# FIT_TCM_SI53301.net
KiCad netlist of a schematic drawn in Altium Designer
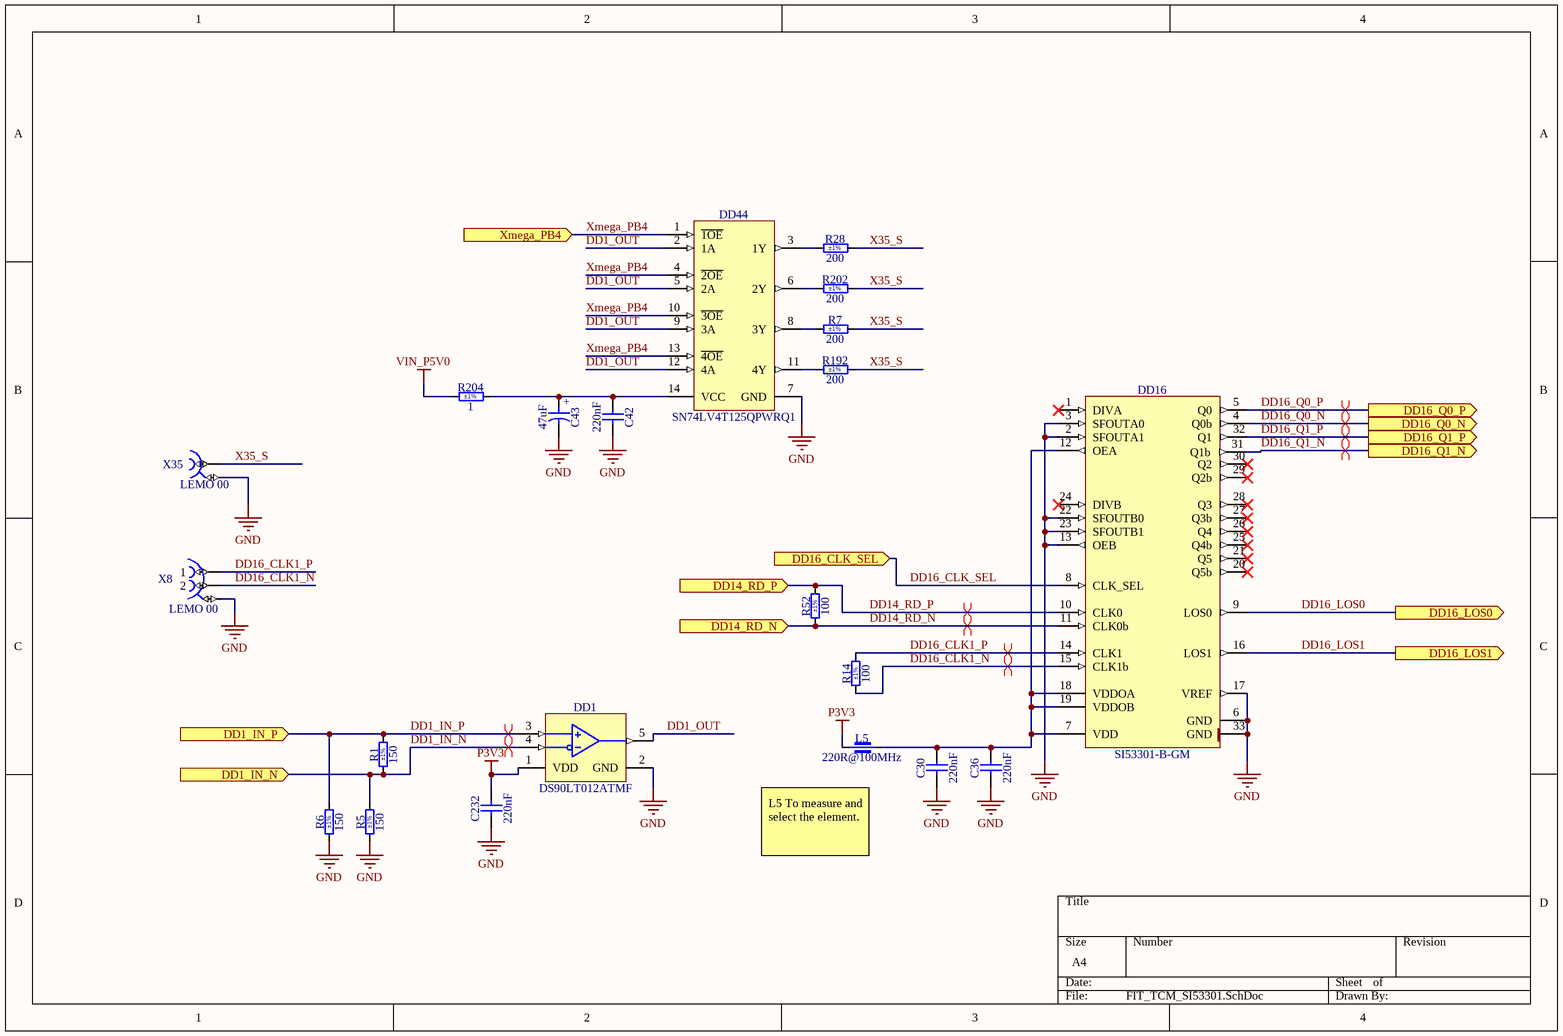
[diagram p0: FIT_TCM_SI53301.SchDoc]

(export (version "E")
  (design (tool "Eeschema 10.0.6"))
  (components
    (comp (ref "C30")
      (value "220nF")
      (footprint "CAPC2012X135N")
      (description "Non-polarised capacitor")
      (fields
        (field (name "PART NUMBER") "CC0805_220NF_50V_10%_X7R")
        (field (name "VOLTAGE") "50V")
        (field (name "AUTHOR") "CERN DEM JLC")
      )
      (libsource (lib "Capacitors") (part "Capacitor - non polarized"))
    )
    (comp (ref "C36")
      (value "220nF")
      (footprint "CAPC2012X135N")
      (description "Non-polarised capacitor")
      (fields
        (field (name "PART NUMBER") "CC0805_220NF_50V_10%_X7R")
        (field (name "VOLTAGE") "50V")
        (field (name "AUTHOR") "CERN DEM JLC")
      )
      (libsource (lib "Capacitors") (part "Capacitor - non polarized"))
    )
    (comp (ref "C42")
      (value "220nF")
      (footprint "CAPC2012X135N")
      (description "Non-polarised capacitor")
      (fields
        (field (name "PART NUMBER") "CC0805_220NF_50V_10%_X7R")
        (field (name "VOLTAGE") "50V")
        (field (name "AUTHOR") "CERN DEM JLC")
      )
      (libsource (lib "Capacitors") (part "Capacitor - non polarized"))
    )
    (comp (ref "C43")
      (value "47uF")
      (footprint "CAPAE530X610N")
      (description "Polarised capacitor")
      (fields
        (field (name "PART NUMBER") "CAE530-610_47UF_16V_20%")
        (field (name "VOLTAGE") "16V")
        (field (name "AUTHOR") "CERN DEM HF")
      )
      (libsource (lib "Capacitors") (part "Capacitor - polarized"))
    )
    (comp (ref "C232")
      (value "220nF")
      (footprint "CAPC2012X135N")
      (description "Non-polarised capacitor")
      (fields
        (field (name "PART NUMBER") "CC0805_220NF_50V_10%_X7R")
        (field (name "VOLTAGE") "50V")
        (field (name "AUTHOR") "CERN DEM JLC")
      )
      (libsource (lib "Capacitors") (part "Capacitor - non polarized"))
    )
    (comp (ref "DD1")
      (value "DS90LT012ATMF")
      (footprint "SOT95P280X145-5N")
      (description "3V LVDS Single CMOS Differential Line Receiver")
      (fields (field (name "MANUFACTURER") "TEXAS INSTRUMENTS") (field (name "AUTHOR") "CERN DEM HF"))
      (libsource (lib "ICs And Semiconductors") (part "DS90LT012A"))
    )
    (comp (ref "DD16")
      (value "SI53301-B-GM")
      (footprint "QFN50P500X500X100-33N-S230")
      (description "I2C-Programmable Any-Frequency, Any-Output Quad Clock Generator")
      (fields (field (name "MANUFACTURER") "SKYWORKS") (field (name "AUTHOR") "CERN DEM HF"))
      (libsource (lib "ICs And Semiconductors") (part "SI53301"))
    )
    (comp (ref "DD44")
      (value "SN74LV4T125QPWRQ1")
      (footprint "SOP65P640X120-14N")
      (description "Quadruple Buffer Translator With 3-State Outputs")
      (fields (field (name "MANUFACTURER") "TEXAS INSTRUMENTS") (field (name "AUTHOR") "CERN DEM HF"))
      (libsource (lib "ICs And Semiconductors") (part "744T125"))
    )
    (comp (ref "L5")
      (value "220R@100MHz")
      (footprint "INDC2012X105N")
      (fields
        (field (name "PART NUMBER") "IND0805_TDK_MPZ2012S221A")
        (field (name "POWER") "3A")
        (field (name "TOLERANCE") "±25%")
        (field (name "AUTHOR") "CERN DEM HF")
      )
      (libsource (lib "Inductors & Transformers") (part "Ferrite Bead"))
    )
    (comp (ref "R1")
      (value "150")
      (footprint "RESC2012X60N")
      (description "Resistor - 1%")
      (fields
        (field (name "TOLERANCE") "±1%")
        (field (name "PART NUMBER") "R0805_150R_1%_0.125W_100PPM")
        (field (name "POWER") "0.125W")
        (field (name "AUTHOR") "CERN DEM JLC")
      )
      (libsource (lib "Resistors") (part "Resistor - 1%"))
    )
    (comp (ref "R5")
      (value "150")
      (footprint "RESC2012X60N")
      (description "Resistor - 1%")
      (fields
        (field (name "TOLERANCE") "±1%")
        (field (name "PART NUMBER") "R0805_150R_1%_0.125W_100PPM")
        (field (name "POWER") "0.125W")
        (field (name "AUTHOR") "CERN DEM JLC")
      )
      (libsource (lib "Resistors") (part "Resistor - 1%"))
    )
    (comp (ref "R6")
      (value "150")
      (footprint "RESC2012X60N")
      (description "Resistor - 1%")
      (fields
        (field (name "TOLERANCE") "±1%")
        (field (name "PART NUMBER") "R0805_150R_1%_0.125W_100PPM")
        (field (name "POWER") "0.125W")
        (field (name "AUTHOR") "CERN DEM JLC")
      )
      (libsource (lib "Resistors") (part "Resistor - 1%"))
    )
    (comp (ref "R7")
      (value "200")
      (footprint "RESC2012X60N")
      (description "Resistor - 1%")
      (fields
        (field (name "TOLERANCE") "±1%")
        (field (name "PART NUMBER") "R0805_200R_1%_0.125W_100PPM")
        (field (name "POWER") "0.125W")
        (field (name "AUTHOR") "CERN DEM JLC")
      )
      (libsource (lib "Resistors") (part "Resistor - 1%"))
    )
    (comp (ref "R14")
      (value "100")
      (footprint "RESC1608X55N")
      (description "Resistor - 1%")
      (fields
        (field (name "TOLERANCE") "±1%")
        (field (name "PART NUMBER") "R0603_100R_1%_0.1W_100PPM")
        (field (name "POWER") "0.1W")
        (field (name "AUTHOR") "CERN DEM JLC")
      )
      (libsource (lib "Resistors") (part "Resistor - 1%"))
    )
    (comp (ref "R28")
      (value "200")
      (footprint "RESC2012X60N")
      (description "Resistor - 1%")
      (fields
        (field (name "TOLERANCE") "±1%")
        (field (name "PART NUMBER") "R0805_200R_1%_0.125W_100PPM")
        (field (name "POWER") "0.125W")
        (field (name "AUTHOR") "CERN DEM JLC")
      )
      (libsource (lib "Resistors") (part "Resistor - 1%"))
    )
    (comp (ref "R52")
      (value "100")
      (footprint "RESC1608X55N")
      (description "Resistor - 1%")
      (fields
        (field (name "TOLERANCE") "±1%")
        (field (name "PART NUMBER") "R0603_100R_1%_0.1W_100PPM")
        (field (name "POWER") "0.1W")
        (field (name "AUTHOR") "CERN DEM JLC")
      )
      (libsource (lib "Resistors") (part "Resistor - 1%"))
    )
    (comp (ref "R192")
      (value "200")
      (footprint "RESC2012X60N")
      (description "Resistor - 1%")
      (fields
        (field (name "TOLERANCE") "±1%")
        (field (name "PART NUMBER") "R0805_200R_1%_0.125W_100PPM")
        (field (name "POWER") "0.125W")
        (field (name "AUTHOR") "CERN DEM JLC")
      )
      (libsource (lib "Resistors") (part "Resistor - 1%"))
    )
    (comp (ref "R202")
      (value "200")
      (footprint "RESC2012X60N")
      (description "Resistor - 1%")
      (fields
        (field (name "TOLERANCE") "±1%")
        (field (name "PART NUMBER") "R0805_200R_1%_0.125W_100PPM")
        (field (name "POWER") "0.125W")
        (field (name "AUTHOR") "CERN DEM JLC")
      )
      (libsource (lib "Resistors") (part "Resistor - 1%"))
    )
    (comp (ref "R204")
      (value "1")
      (footprint "RESC2012X60N")
      (description "Resistor - 1%")
      (fields
        (field (name "TOLERANCE") "±1%")
        (field (name "PART NUMBER") "R0805_1R_1%_0.125W_100PPM")
        (field (name "POWER") "0.125W")
        (field (name "AUTHOR") "CERN DEM HF")
      )
      (libsource (lib "Resistors") (part "Resistor - 1%"))
    )
    (comp (ref "X8")
      (value "LEMO 00")
      (footprint "LEMO_EPG.00.302.NLN")
      (fields
        (field (name "PART NUMBER") "LEMO_EPG.00.302.NLN")
        (field (name "MANUFACTURER") "LEMO")
        (field (name "MANUFACTURER PART NUMBER") "EPG.00.302.NLN")
        (field (name "AUTHOR") "CERN DEM JLC")
      )
      (libsource (lib "Connectors") (part "Coax_2Female_1Shield"))
    )
    (comp (ref "X35")
      (value "LEMO 00")
      (footprint "LEMO_EPL.00.250.NTN")
      (fields
        (field (name "PART NUMBER") "LEMO_EPL.00.250.NTN")
        (field (name "MANUFACTURER") "LEMO")
        (field (name "MANUFACTURER PART NUMBER") "EPL.00.250.NTN")
        (field (name "AUTHOR") "CERN DEM JLC")
      )
      (libsource (lib "Connectors") (part "Coax_1Female_1Shield"))
    )
  )
  (nets
    (net (code "1") (name "/DD1_IN_N") (class "Default")
      (node (ref "DD1") (pin "4") (pinfunction "IN-_4") (pintype "input"))
      (node (ref "R1") (pin "1") (pinfunction "1_1") (pintype "passive"))
      (node (ref "R5") (pin "2") (pinfunction "2_2") (pintype "passive"))
    )
    (net (code "2") (name "/DD1_IN_P") (class "Default")
      (node (ref "DD1") (pin "3") (pinfunction "IN+_3") (pintype "input"))
      (node (ref "R1") (pin "2") (pinfunction "2_2") (pintype "passive"))
      (node (ref "R6") (pin "2") (pinfunction "2_2") (pintype "passive"))
    )
    (net (code "3") (name "/DD1_OUT") (class "Default")
      (node (ref "DD1") (pin "5") (pinfunction "TTLOUT_5") (pintype "output"))
      (node (ref "DD44") (pin "12") (pinfunction "4A_12") (pintype "input"))
      (node (ref "DD44") (pin "2") (pinfunction "1A_2") (pintype "input"))
      (node (ref "DD44") (pin "5") (pinfunction "2A_5") (pintype "input"))
      (node (ref "DD44") (pin "9") (pinfunction "3A_9") (pintype "input"))
    )
    (net (code "4") (name "/DD14_RD_N") (class "Default")
      (node (ref "DD16") (pin "11") (pinfunction "CLK0b_11") (pintype "input"))
      (node (ref "R52") (pin "1") (pinfunction "1_1") (pintype "passive"))
    )
    (net (code "5") (name "/DD14_RD_P") (class "Default")
      (node (ref "DD16") (pin "10") (pinfunction "CLK0_10") (pintype "input"))
      (node (ref "R52") (pin "2") (pinfunction "2_2") (pintype "passive"))
    )
    (net (code "6") (name "/DD16_CLK1_N") (class "Default")
      (node (ref "DD16") (pin "15") (pinfunction "CLK1b_15") (pintype "input"))
      (node (ref "R14") (pin "1") (pinfunction "1_1") (pintype "passive"))
      (node (ref "X8") (pin "2") (pinfunction "2_2") (pintype "bidirectional"))
    )
    (net (code "7") (name "/DD16_CLK1_P") (class "Default")
      (node (ref "DD16") (pin "14") (pinfunction "CLK1_14") (pintype "input"))
      (node (ref "R14") (pin "2") (pinfunction "2_2") (pintype "passive"))
      (node (ref "X8") (pin "1") (pinfunction "1_1") (pintype "bidirectional"))
    )
    (net (code "8") (name "/DD16_CLK_SEL") (class "Default")
      (node (ref "DD16") (pin "8") (pinfunction "CLK_SEL_8") (pintype "input"))
    )
    (net (code "9") (name "/DD16_LOS0") (class "Default")
      (node (ref "DD16") (pin "9") (pinfunction "LOS0_9") (pintype "output"))
    )
    (net (code "10") (name "/DD16_LOS1") (class "Default")
      (node (ref "DD16") (pin "16") (pinfunction "LOS1_16") (pintype "output"))
    )
    (net (code "11") (name "/DD16_Q0_N") (class "Default")
      (node (ref "DD16") (pin "4") (pinfunction "Q0b_4") (pintype "output"))
    )
    (net (code "12") (name "/DD16_Q0_P") (class "Default")
      (node (ref "DD16") (pin "5") (pinfunction "Q0_5") (pintype "output"))
    )
    (net (code "13") (name "/DD16_Q1_N") (class "Default")
      (node (ref "DD16") (pin "31") (pinfunction "Q1b_31") (pintype "output"))
    )
    (net (code "14") (name "/DD16_Q1_P") (class "Default")
      (node (ref "DD16") (pin "32") (pinfunction "Q1_32") (pintype "output"))
    )
    (net (code "15") (name "/X35_S") (class "Default")
      (node (ref "R192") (pin "2") (pinfunction "2_2") (pintype "passive"))
      (node (ref "R202") (pin "2") (pinfunction "2_2") (pintype "passive"))
      (node (ref "R28") (pin "2") (pinfunction "2_2") (pintype "passive"))
      (node (ref "R7") (pin "2") (pinfunction "2_2") (pintype "passive"))
      (node (ref "X35") (pin "1") (pinfunction "1_1") (pintype "bidirectional"))
    )
    (net (code "16") (name "/Xmega_PB4") (class "Default")
      (node (ref "DD44") (pin "1") (pinfunction "~{1OE}_1") (pintype "input"))
      (node (ref "DD44") (pin "10") (pinfunction "~{3OE}_10") (pintype "input"))
      (node (ref "DD44") (pin "13") (pinfunction "~{4OE}_13") (pintype "input"))
      (node (ref "DD44") (pin "4") (pinfunction "~{2OE}_4") (pintype "input"))
    )
    (net (code "17") (name "GND") (class "Default")
      (node (ref "C232") (pin "1") (pinfunction "1_1") (pintype "passive"))
      (node (ref "C30") (pin "1") (pinfunction "1_1") (pintype "passive"))
      (node (ref "C36") (pin "1") (pinfunction "1_1") (pintype "passive"))
      (node (ref "C42") (pin "2") (pinfunction "2_2") (pintype "passive"))
      (node (ref "C43") (pin "2") (pinfunction "2_2") (pintype "passive"))
      (node (ref "DD1") (pin "2") (pinfunction "GND_2") (pintype "power_in"))
      (node (ref "DD16") (pin "13") (pinfunction "OEB_13") (pintype "output"))
      (node (ref "DD16") (pin "17") (pinfunction "VREF_17") (pintype "output"))
      (node (ref "DD16") (pin "2") (pinfunction "SFOUTA1_2") (pintype "input"))
      (node (ref "DD16") (pin "22") (pinfunction "SFOUTB0_22") (pintype "input"))
      (node (ref "DD16") (pin "23") (pinfunction "SFOUTB1_23") (pintype "input"))
      (node (ref "DD16") (pin "3") (pinfunction "SFOUTA0_3") (pintype "input"))
      (node (ref "DD16") (pin "33") (pinfunction "GND_33") (pintype "power_in"))
      (node (ref "DD16") (pin "6") (pinfunction "GND_6") (pintype "power_in"))
      (node (ref "DD44") (pin "7") (pinfunction "GND_7") (pintype "power_in"))
      (node (ref "R5") (pin "1") (pinfunction "1_1") (pintype "passive"))
      (node (ref "R6") (pin "1") (pinfunction "1_1") (pintype "passive"))
      (node (ref "X35") (pin "2") (pinfunction "2_2") (pintype "bidirectional"))
      (node (ref "X8") (pin "3") (pinfunction "3_3") (pintype "bidirectional"))
    )
    (net (code "18") (name "Net-(DD16-OEA)") (class "Default")
      (node (ref "C30") (pin "2") (pinfunction "2_2") (pintype "passive"))
      (node (ref "C36") (pin "2") (pinfunction "2_2") (pintype "passive"))
      (node (ref "DD16") (pin "12") (pinfunction "OEA_12") (pintype "output"))
      (node (ref "DD16") (pin "18") (pinfunction "VDDOA_18") (pintype "power_in"))
      (node (ref "DD16") (pin "19") (pinfunction "VDDOB_19") (pintype "power_in"))
      (node (ref "DD16") (pin "7") (pinfunction "VDD_7") (pintype "power_in"))
      (node (ref "L5") (pin "2") (pinfunction "2_2") (pintype "passive"))
    )
    (net (code "19") (name "Net-(DD44-1Y)") (class "Default")
      (node (ref "DD44") (pin "3") (pinfunction "1Y_3") (pintype "output"))
      (node (ref "R28") (pin "1") (pinfunction "1_1") (pintype "passive"))
    )
    (net (code "20") (name "Net-(DD44-2Y)") (class "Default")
      (node (ref "DD44") (pin "6") (pinfunction "2Y_6") (pintype "output"))
      (node (ref "R202") (pin "1") (pinfunction "1_1") (pintype "passive"))
    )
    (net (code "21") (name "Net-(DD44-3Y)") (class "Default")
      (node (ref "DD44") (pin "8") (pinfunction "3Y_8") (pintype "output"))
      (node (ref "R7") (pin "1") (pinfunction "1_1") (pintype "passive"))
    )
    (net (code "22") (name "Net-(DD44-4Y)") (class "Default")
      (node (ref "DD44") (pin "11") (pinfunction "4Y_11") (pintype "output"))
      (node (ref "R192") (pin "1") (pinfunction "1_1") (pintype "passive"))
    )
    (net (code "23") (name "Net-(DD44-VCC)") (class "Default")
      (node (ref "C42") (pin "1") (pinfunction "1_1") (pintype "passive"))
      (node (ref "C43") (pin "1") (pinfunction "1_1") (pintype "passive"))
      (node (ref "DD44") (pin "14") (pinfunction "VCC_14") (pintype "power_in"))
      (node (ref "R204") (pin "2") (pinfunction "2_2") (pintype "passive"))
    )
    (net (code "24") (name "P3V3") (class "Default")
      (node (ref "C232") (pin "2") (pinfunction "2_2") (pintype "passive"))
      (node (ref "DD1") (pin "1") (pinfunction "VDD_1") (pintype "power_in"))
      (node (ref "L5") (pin "1") (pinfunction "1_1") (pintype "passive"))
    )
    (net (code "25") (name "VIN_P5V0") (class "Default")
      (node (ref "R204") (pin "1") (pinfunction "1_1") (pintype "passive"))
    )
    (net (code "26") (name "unconnected-(DD16-DIVA-Pad1)") (class "Default")
      (node (ref "DD16") (pin "1") (pinfunction "DIVA_1") (pintype "input+no_connect"))
    )
    (net (code "27") (name "unconnected-(DD16-DIVB-Pad24)") (class "Default")
      (node (ref "DD16") (pin "24") (pinfunction "DIVB_24") (pintype "input+no_connect"))
    )
    (net (code "28") (name "unconnected-(DD16-Q2-Pad30)") (class "Default")
      (node (ref "DD16") (pin "30") (pinfunction "Q2_30") (pintype "output+no_connect"))
    )
    (net (code "29") (name "unconnected-(DD16-Q2b-Pad29)") (class "Default")
      (node (ref "DD16") (pin "29") (pinfunction "Q2b_29") (pintype "output+no_connect"))
    )
    (net (code "30") (name "unconnected-(DD16-Q3-Pad28)") (class "Default")
      (node (ref "DD16") (pin "28") (pinfunction "Q3_28") (pintype "output+no_connect"))
    )
    (net (code "31") (name "unconnected-(DD16-Q3b-Pad27)") (class "Default")
      (node (ref "DD16") (pin "27") (pinfunction "Q3b_27") (pintype "output+no_connect"))
    )
    (net (code "32") (name "unconnected-(DD16-Q4-Pad26)") (class "Default")
      (node (ref "DD16") (pin "26") (pinfunction "Q4_26") (pintype "output+no_connect"))
    )
    (net (code "33") (name "unconnected-(DD16-Q4b-Pad25)") (class "Default")
      (node (ref "DD16") (pin "25") (pinfunction "Q4b_25") (pintype "output+no_connect"))
    )
    (net (code "34") (name "unconnected-(DD16-Q5-Pad21)") (class "Default")
      (node (ref "DD16") (pin "21") (pinfunction "Q5_21") (pintype "output+no_connect"))
    )
    (net (code "35") (name "unconnected-(DD16-Q5b-Pad20)") (class "Default")
      (node (ref "DD16") (pin "20") (pinfunction "Q5b_20") (pintype "output+no_connect"))
    )
  )
)
